# 07_LMS7002M_Power.net
KiCad netlist of a schematic drawn in Altium Designer
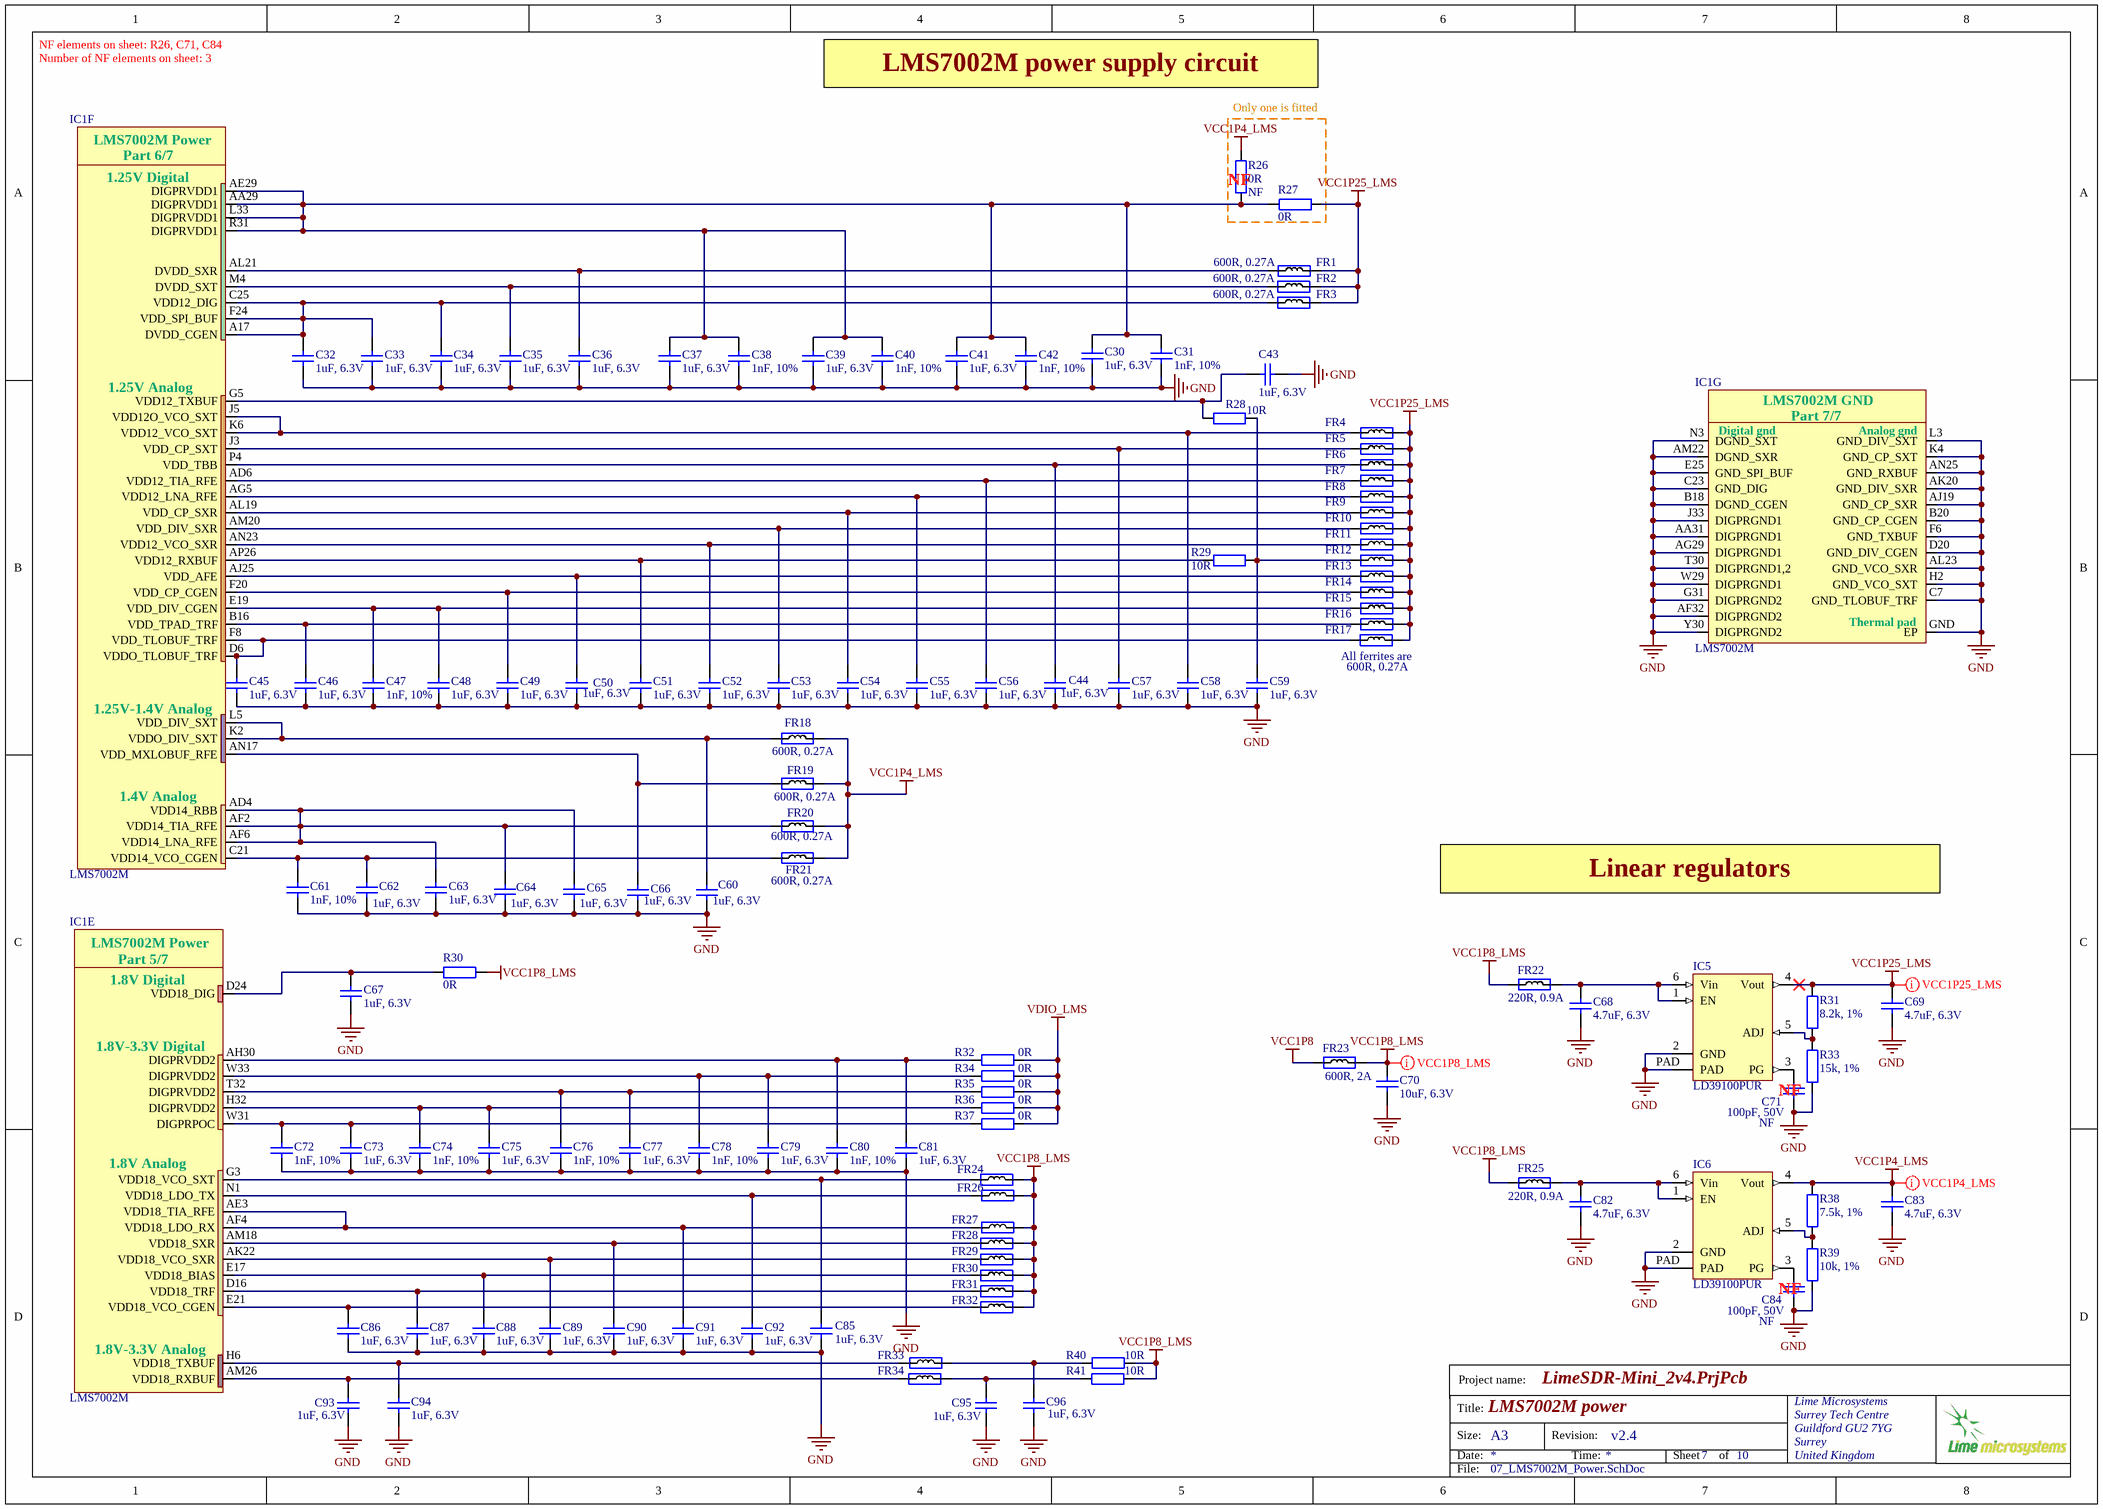
[diagram p0: 07_LMS7002M_Power.SchDoc]

(export (version "E")
  (design (tool "Eeschema 10.0.6"))
  (components
    (comp (ref "C30")
      (value "1uF, 6.3V")
      (footprint "CAP0201")
      (fields (field (name "TOLERANCE") "±20%") (field (name "MANUFACTURER") "TDK Corporation"))
      (libsource (lib "LimeMicroAltiumLib_schLib") (part "Cap_0402"))
    )
    (comp (ref "C31")
      (value "1nF, 10%")
      (footprint "CAP0201")
      (fields (field (name "TOLERANCE") "±10%") (field (name "MANUFACTURER") "TDK Corporation"))
      (libsource (lib "LimeMicroAltiumLib_schLib") (part "Cap_0402"))
    )
    (comp (ref "C32")
      (value "1uF, 6.3V")
      (footprint "CAP0201")
      (fields (field (name "TOLERANCE") "±20%") (field (name "MANUFACTURER") "TDK Corporation"))
      (libsource (lib "LimeMicroAltiumLib_schLib") (part "Cap_0402"))
    )
    (comp (ref "C33")
      (value "1uF, 6.3V")
      (footprint "CAP0201")
      (fields (field (name "TOLERANCE") "±20%") (field (name "MANUFACTURER") "TDK Corporation"))
      (libsource (lib "LimeMicroAltiumLib_schLib") (part "Cap_0402"))
    )
    (comp (ref "C34")
      (value "1uF, 6.3V")
      (footprint "CAP0201")
      (fields (field (name "TOLERANCE") "±20%") (field (name "MANUFACTURER") "TDK Corporation"))
      (libsource (lib "LimeMicroAltiumLib_schLib") (part "Cap_0402"))
    )
    (comp (ref "C35")
      (value "1uF, 6.3V")
      (footprint "CAP0201")
      (fields (field (name "TOLERANCE") "±20%") (field (name "MANUFACTURER") "TDK Corporation"))
      (libsource (lib "LimeMicroAltiumLib_schLib") (part "Cap_0402"))
    )
    (comp (ref "C36")
      (value "1uF, 6.3V")
      (footprint "CAP0201")
      (fields (field (name "TOLERANCE") "±20%") (field (name "MANUFACTURER") "TDK Corporation"))
      (libsource (lib "LimeMicroAltiumLib_schLib") (part "Cap_0402"))
    )
    (comp (ref "C37")
      (value "1uF, 6.3V")
      (footprint "CAP0201")
      (fields (field (name "TOLERANCE") "±20%") (field (name "MANUFACTURER") "TDK Corporation"))
      (libsource (lib "LimeMicroAltiumLib_schLib") (part "Cap_0402"))
    )
    (comp (ref "C38")
      (value "1nF, 10%")
      (footprint "CAP0201")
      (fields (field (name "TOLERANCE") "±10%") (field (name "MANUFACTURER") "TDK Corporation"))
      (libsource (lib "LimeMicroAltiumLib_schLib") (part "Cap_0402"))
    )
    (comp (ref "C39")
      (value "1uF, 6.3V")
      (footprint "CAP0201")
      (fields (field (name "TOLERANCE") "±20%") (field (name "MANUFACTURER") "TDK Corporation"))
      (libsource (lib "LimeMicroAltiumLib_schLib") (part "Cap_0402"))
    )
    (comp (ref "C40")
      (value "1nF, 10%")
      (footprint "CAP0201")
      (fields (field (name "TOLERANCE") "±10%") (field (name "MANUFACTURER") "TDK Corporation"))
      (libsource (lib "LimeMicroAltiumLib_schLib") (part "Cap_0402"))
    )
    (comp (ref "C41")
      (value "1uF, 6.3V")
      (footprint "CAP0201")
      (fields (field (name "TOLERANCE") "±20%") (field (name "MANUFACTURER") "TDK Corporation"))
      (libsource (lib "LimeMicroAltiumLib_schLib") (part "Cap_0402"))
    )
    (comp (ref "C42")
      (value "1nF, 10%")
      (footprint "CAP0201")
      (fields (field (name "TOLERANCE") "±10%") (field (name "MANUFACTURER") "TDK Corporation"))
      (libsource (lib "LimeMicroAltiumLib_schLib") (part "Cap_0402"))
    )
    (comp (ref "C43")
      (value "1uF, 6.3V")
      (footprint "CAP0201")
      (fields (field (name "TOLERANCE") "±20%") (field (name "MANUFACTURER") "TDK Corporation"))
      (libsource (lib "LimeMicroAltiumLib_schLib") (part "Cap_0402"))
    )
    (comp (ref "C44")
      (value "1uF, 6.3V")
      (footprint "CAP0201")
      (fields (field (name "TOLERANCE") "±20%") (field (name "MANUFACTURER") "TDK Corporation"))
      (libsource (lib "LimeMicroAltiumLib_schLib") (part "Cap_0402"))
    )
    (comp (ref "C45")
      (value "1uF, 6.3V")
      (footprint "CAP0201")
      (fields (field (name "TOLERANCE") "±20%") (field (name "MANUFACTURER") "TDK Corporation"))
      (libsource (lib "LimeMicroAltiumLib_schLib") (part "Cap_0402"))
    )
    (comp (ref "C46")
      (value "1uF, 6.3V")
      (footprint "CAP0201")
      (fields (field (name "TOLERANCE") "±20%") (field (name "MANUFACTURER") "TDK Corporation"))
      (libsource (lib "LimeMicroAltiumLib_schLib") (part "Cap_0402"))
    )
    (comp (ref "C47")
      (value "1nF, 10%")
      (footprint "CAP0201")
      (fields (field (name "TOLERANCE") "±10%") (field (name "MANUFACTURER") "TDK Corporation"))
      (libsource (lib "LimeMicroAltiumLib_schLib") (part "Cap_0402"))
    )
    (comp (ref "C48")
      (value "1uF, 6.3V")
      (footprint "CAP0201")
      (fields (field (name "TOLERANCE") "±20%") (field (name "MANUFACTURER") "TDK Corporation"))
      (libsource (lib "LimeMicroAltiumLib_schLib") (part "Cap_0402"))
    )
    (comp (ref "C49")
      (value "1uF, 6.3V")
      (footprint "CAP0201")
      (fields (field (name "TOLERANCE") "±20%") (field (name "MANUFACTURER") "TDK Corporation"))
      (libsource (lib "LimeMicroAltiumLib_schLib") (part "Cap_0402"))
    )
    (comp (ref "C50")
      (value "1uF, 6.3V")
      (footprint "CAP0201")
      (fields (field (name "TOLERANCE") "±20%") (field (name "MANUFACTURER") "TDK Corporation"))
      (libsource (lib "LimeMicroAltiumLib_schLib") (part "Cap_0402"))
    )
    (comp (ref "C51")
      (value "1uF, 6.3V")
      (footprint "CAP0201")
      (fields (field (name "TOLERANCE") "±20%") (field (name "MANUFACTURER") "TDK Corporation"))
      (libsource (lib "LimeMicroAltiumLib_schLib") (part "Cap_0402"))
    )
    (comp (ref "C52")
      (value "1uF, 6.3V")
      (footprint "CAP0201")
      (fields (field (name "TOLERANCE") "±20%") (field (name "MANUFACTURER") "TDK Corporation"))
      (libsource (lib "LimeMicroAltiumLib_schLib") (part "Cap_0402"))
    )
    (comp (ref "C53")
      (value "1uF, 6.3V")
      (footprint "CAP0201")
      (fields (field (name "TOLERANCE") "±20%") (field (name "MANUFACTURER") "TDK Corporation"))
      (libsource (lib "LimeMicroAltiumLib_schLib") (part "Cap_0402"))
    )
    (comp (ref "C54")
      (value "1uF, 6.3V")
      (footprint "CAP0201")
      (fields (field (name "TOLERANCE") "±20%") (field (name "MANUFACTURER") "TDK Corporation"))
      (libsource (lib "LimeMicroAltiumLib_schLib") (part "Cap_0402"))
    )
    (comp (ref "C55")
      (value "1uF, 6.3V")
      (footprint "CAP0201")
      (fields (field (name "TOLERANCE") "±20%") (field (name "MANUFACTURER") "TDK Corporation"))
      (libsource (lib "LimeMicroAltiumLib_schLib") (part "Cap_0402"))
    )
    (comp (ref "C56")
      (value "1uF, 6.3V")
      (footprint "CAP0201")
      (fields (field (name "TOLERANCE") "±20%") (field (name "MANUFACTURER") "TDK Corporation"))
      (libsource (lib "LimeMicroAltiumLib_schLib") (part "Cap_0402"))
    )
    (comp (ref "C57")
      (value "1uF, 6.3V")
      (footprint "CAP0201")
      (fields (field (name "TOLERANCE") "±20%") (field (name "MANUFACTURER") "TDK Corporation"))
      (libsource (lib "LimeMicroAltiumLib_schLib") (part "Cap_0402"))
    )
    (comp (ref "C58")
      (value "1uF, 6.3V")
      (footprint "CAP0201")
      (fields (field (name "TOLERANCE") "±20%") (field (name "MANUFACTURER") "TDK Corporation"))
      (libsource (lib "LimeMicroAltiumLib_schLib") (part "Cap_0402"))
    )
    (comp (ref "C59")
      (value "1uF, 6.3V")
      (footprint "CAP0201")
      (fields (field (name "TOLERANCE") "±20%") (field (name "MANUFACTURER") "TDK Corporation"))
      (libsource (lib "LimeMicroAltiumLib_schLib") (part "Cap_0402"))
    )
    (comp (ref "C60")
      (value "1uF, 6.3V")
      (footprint "CAP0201")
      (fields (field (name "TOLERANCE") "±20%") (field (name "MANUFACTURER") "TDK Corporation"))
      (libsource (lib "LimeMicroAltiumLib_schLib") (part "Cap_0402"))
    )
    (comp (ref "C61")
      (value "1nF, 10%")
      (footprint "CAP0201")
      (fields (field (name "TOLERANCE") "±10%") (field (name "MANUFACTURER") "TDK Corporation"))
      (libsource (lib "LimeMicroAltiumLib_schLib") (part "Cap_0402"))
    )
    (comp (ref "C62")
      (value "1uF, 6.3V")
      (footprint "CAP0201")
      (fields (field (name "TOLERANCE") "±20%") (field (name "MANUFACTURER") "TDK Corporation"))
      (libsource (lib "LimeMicroAltiumLib_schLib") (part "Cap_0402"))
    )
    (comp (ref "C63")
      (value "1uF, 6.3V")
      (footprint "CAP0201")
      (fields (field (name "TOLERANCE") "±20%") (field (name "MANUFACTURER") "TDK Corporation"))
      (libsource (lib "LimeMicroAltiumLib_schLib") (part "Cap_0402"))
    )
    (comp (ref "C64")
      (value "1uF, 6.3V")
      (footprint "CAP0201")
      (fields (field (name "TOLERANCE") "±20%") (field (name "MANUFACTURER") "TDK Corporation"))
      (libsource (lib "LimeMicroAltiumLib_schLib") (part "Cap_0402"))
    )
    (comp (ref "C65")
      (value "1uF, 6.3V")
      (footprint "CAP0201")
      (fields (field (name "TOLERANCE") "±20%") (field (name "MANUFACTURER") "TDK Corporation"))
      (libsource (lib "LimeMicroAltiumLib_schLib") (part "Cap_0402"))
    )
    (comp (ref "C66")
      (value "1uF, 6.3V")
      (footprint "CAP0201")
      (fields (field (name "TOLERANCE") "±20%") (field (name "MANUFACTURER") "TDK Corporation"))
      (libsource (lib "LimeMicroAltiumLib_schLib") (part "Cap_0402"))
    )
    (comp (ref "C67")
      (value "1uF, 6.3V")
      (footprint "CAP0201")
      (fields (field (name "TOLERANCE") "±20%") (field (name "MANUFACTURER") "TDK Corporation"))
      (libsource (lib "LimeMicroAltiumLib_schLib") (part "Cap_0402"))
    )
    (comp (ref "C68")
      (value "4.7uF, 6.3V")
      (footprint "CAP0402")
      (fields
        (field (name "MANUFACTURER") "Murata Electronics North America")
        (field (name "TOLERANCE") "±20%")
      )
      (libsource (lib "LimeMicroAltiumLib_schLib") (part "Cap_0402"))
    )
    (comp (ref "C69")
      (value "4.7uF, 6.3V")
      (footprint "CAP0402")
      (fields
        (field (name "MANUFACTURER") "Murata Electronics North America")
        (field (name "TOLERANCE") "±20%")
      )
      (libsource (lib "LimeMicroAltiumLib_schLib") (part "Cap_0402"))
    )
    (comp (ref "C70")
      (value "10uF, 6.3V")
      (footprint "CAP0603")
      (fields (field (name "TOLERANCE") "±20%") (field (name "MANUFACTURER") "Yageo"))
      (libsource (lib "LimeFPGAboard_schLib") (part "Cap_0603"))
    )
    (comp (ref "C71")
      (value "100pF, 50V")
      (footprint "CAP0402")
      (fields
        (field (name "ASSEMBLY INFO") "NF")
        (field (name "MANUFACTURER") "Yageo")
        (field (name "TOLERANCE") "±5%")
      )
      (libsource (lib "LimeMicroAltiumLib_schLib") (part "Cap_0402"))
    )
    (comp (ref "C72")
      (value "1nF, 10%")
      (footprint "CAP0201")
      (fields (field (name "TOLERANCE") "±10%") (field (name "MANUFACTURER") "TDK Corporation"))
      (libsource (lib "LimeMicroAltiumLib_schLib") (part "Cap_0402"))
    )
    (comp (ref "C73")
      (value "1uF, 6.3V")
      (footprint "CAP0201")
      (fields (field (name "TOLERANCE") "±20%") (field (name "MANUFACTURER") "TDK Corporation"))
      (libsource (lib "LimeMicroAltiumLib_schLib") (part "Cap_0402"))
    )
    (comp (ref "C74")
      (value "1nF, 10%")
      (footprint "CAP0201")
      (fields (field (name "TOLERANCE") "±10%") (field (name "MANUFACTURER") "TDK Corporation"))
      (libsource (lib "LimeMicroAltiumLib_schLib") (part "Cap_0402"))
    )
    (comp (ref "C75")
      (value "1uF, 6.3V")
      (footprint "CAP0201")
      (fields (field (name "TOLERANCE") "±20%") (field (name "MANUFACTURER") "TDK Corporation"))
      (libsource (lib "LimeMicroAltiumLib_schLib") (part "Cap_0402"))
    )
    (comp (ref "C76")
      (value "1nF, 10%")
      (footprint "CAP0201")
      (fields (field (name "TOLERANCE") "±10%") (field (name "MANUFACTURER") "TDK Corporation"))
      (libsource (lib "LimeMicroAltiumLib_schLib") (part "Cap_0402"))
    )
    (comp (ref "C77")
      (value "1uF, 6.3V")
      (footprint "CAP0201")
      (fields (field (name "TOLERANCE") "±20%") (field (name "MANUFACTURER") "TDK Corporation"))
      (libsource (lib "LimeMicroAltiumLib_schLib") (part "Cap_0402"))
    )
    (comp (ref "C78")
      (value "1nF, 10%")
      (footprint "CAP0201")
      (fields (field (name "TOLERANCE") "±10%") (field (name "MANUFACTURER") "TDK Corporation"))
      (libsource (lib "LimeMicroAltiumLib_schLib") (part "Cap_0402"))
    )
    (comp (ref "C79")
      (value "1uF, 6.3V")
      (footprint "CAP0201")
      (fields (field (name "TOLERANCE") "±20%") (field (name "MANUFACTURER") "TDK Corporation"))
      (libsource (lib "LimeMicroAltiumLib_schLib") (part "Cap_0402"))
    )
    (comp (ref "C80")
      (value "1nF, 10%")
      (footprint "CAP0201")
      (fields (field (name "TOLERANCE") "±10%") (field (name "MANUFACTURER") "TDK Corporation"))
      (libsource (lib "LimeMicroAltiumLib_schLib") (part "Cap_0402"))
    )
    (comp (ref "C81")
      (value "1uF, 6.3V")
      (footprint "CAP0201")
      (fields (field (name "TOLERANCE") "±20%") (field (name "MANUFACTURER") "TDK Corporation"))
      (libsource (lib "LimeMicroAltiumLib_schLib") (part "Cap_0402"))
    )
    (comp (ref "C82")
      (value "4.7uF, 6.3V")
      (footprint "CAP0402")
      (fields
        (field (name "MANUFACTURER") "Murata Electronics North America")
        (field (name "TOLERANCE") "±20%")
      )
      (libsource (lib "LimeMicroAltiumLib_schLib") (part "Cap_0402"))
    )
    (comp (ref "C83")
      (value "4.7uF, 6.3V")
      (footprint "CAP0402")
      (fields
        (field (name "MANUFACTURER") "Murata Electronics North America")
        (field (name "TOLERANCE") "±20%")
      )
      (libsource (lib "LimeMicroAltiumLib_schLib") (part "Cap_0402"))
    )
    (comp (ref "C84")
      (value "100pF, 50V")
      (footprint "CAP0402")
      (fields
        (field (name "ASSEMBLY INFO") "NF")
        (field (name "MANUFACTURER") "Yageo")
        (field (name "TOLERANCE") "±5%")
      )
      (libsource (lib "LimeMicroAltiumLib_schLib") (part "Cap_0402"))
    )
    (comp (ref "C85")
      (value "1uF, 6.3V")
      (footprint "CAP0201")
      (fields (field (name "TOLERANCE") "±20%") (field (name "MANUFACTURER") "TDK Corporation"))
      (libsource (lib "LimeMicroAltiumLib_schLib") (part "Cap_0402"))
    )
    (comp (ref "C86")
      (value "1uF, 6.3V")
      (footprint "CAP0201")
      (fields (field (name "TOLERANCE") "±20%") (field (name "MANUFACTURER") "TDK Corporation"))
      (libsource (lib "LimeMicroAltiumLib_schLib") (part "Cap_0402"))
    )
    (comp (ref "C87")
      (value "1uF, 6.3V")
      (footprint "CAP0201")
      (fields (field (name "TOLERANCE") "±20%") (field (name "MANUFACTURER") "TDK Corporation"))
      (libsource (lib "LimeMicroAltiumLib_schLib") (part "Cap_0402"))
    )
    (comp (ref "C88")
      (value "1uF, 6.3V")
      (footprint "CAP0201")
      (fields (field (name "TOLERANCE") "±20%") (field (name "MANUFACTURER") "TDK Corporation"))
      (libsource (lib "LimeMicroAltiumLib_schLib") (part "Cap_0402"))
    )
    (comp (ref "C89")
      (value "1uF, 6.3V")
      (footprint "CAP0201")
      (fields (field (name "TOLERANCE") "±20%") (field (name "MANUFACTURER") "TDK Corporation"))
      (libsource (lib "LimeMicroAltiumLib_schLib") (part "Cap_0402"))
    )
    (comp (ref "C90")
      (value "1uF, 6.3V")
      (footprint "CAP0201")
      (fields (field (name "TOLERANCE") "±20%") (field (name "MANUFACTURER") "TDK Corporation"))
      (libsource (lib "LimeMicroAltiumLib_schLib") (part "Cap_0402"))
    )
    (comp (ref "C91")
      (value "1uF, 6.3V")
      (footprint "CAP0201")
      (fields (field (name "TOLERANCE") "±20%") (field (name "MANUFACTURER") "TDK Corporation"))
      (libsource (lib "LimeMicroAltiumLib_schLib") (part "Cap_0402"))
    )
    (comp (ref "C92")
      (value "1uF, 6.3V")
      (footprint "CAP0201")
      (fields (field (name "TOLERANCE") "±20%") (field (name "MANUFACTURER") "TDK Corporation"))
      (libsource (lib "LimeMicroAltiumLib_schLib") (part "Cap_0402"))
    )
    (comp (ref "C93")
      (value "1uF, 6.3V")
      (footprint "CAP0201")
      (fields (field (name "TOLERANCE") "±20%") (field (name "MANUFACTURER") "TDK Corporation"))
      (libsource (lib "LimeMicroAltiumLib_schLib") (part "Cap_0402"))
    )
    (comp (ref "C94")
      (value "1uF, 6.3V")
      (footprint "CAP0201")
      (fields (field (name "TOLERANCE") "±20%") (field (name "MANUFACTURER") "TDK Corporation"))
      (libsource (lib "LimeMicroAltiumLib_schLib") (part "Cap_0402"))
    )
    (comp (ref "C95")
      (value "1uF, 6.3V")
      (footprint "CAP0201")
      (fields (field (name "TOLERANCE") "±20%") (field (name "MANUFACTURER") "TDK Corporation"))
      (libsource (lib "LimeMicroAltiumLib_schLib") (part "Cap_0402"))
    )
    (comp (ref "C96")
      (value "1uF, 6.3V")
      (footprint "CAP0201")
      (fields (field (name "TOLERANCE") "±20%") (field (name "MANUFACTURER") "TDK Corporation"))
      (libsource (lib "LimeMicroAltiumLib_schLib") (part "Cap_0402"))
    )
    (comp (ref "FR1")
      (value "600R, 0.27A")
      (footprint "RES0201")
      (fields (field (name "MANUFACTURER") "Taiyo Yuden"))
      (libsource (lib "LimeMicroAltiumLib_schLib") (part "Ferrite"))
    )
    (comp (ref "FR2")
      (value "600R, 0.27A")
      (footprint "RES0201")
      (fields (field (name "MANUFACTURER") "Taiyo Yuden"))
      (libsource (lib "LimeMicroAltiumLib_schLib") (part "Ferrite"))
    )
    (comp (ref "FR3")
      (value "600R, 0.27A")
      (footprint "RES0201")
      (fields (field (name "MANUFACTURER") "Taiyo Yuden"))
      (libsource (lib "LimeMicroAltiumLib_schLib") (part "Ferrite"))
    )
    (comp (ref "FR4")
      (value "600R, 0.27A")
      (footprint "RES0201")
      (fields (field (name "MANUFACTURER") "Taiyo Yuden"))
      (libsource (lib "LimeMicroAltiumLib_schLib") (part "Ferrite"))
    )
    (comp (ref "FR5")
      (value "600R, 0.27A")
      (footprint "RES0201")
      (fields (field (name "MANUFACTURER") "Taiyo Yuden"))
      (libsource (lib "LimeMicroAltiumLib_schLib") (part "Ferrite"))
    )
    (comp (ref "FR6")
      (value "600R, 0.27A")
      (footprint "RES0201")
      (fields (field (name "MANUFACTURER") "Taiyo Yuden"))
      (libsource (lib "LimeMicroAltiumLib_schLib") (part "Ferrite"))
    )
    (comp (ref "FR7")
      (value "600R, 0.27A")
      (footprint "RES0201")
      (fields (field (name "MANUFACTURER") "Taiyo Yuden"))
      (libsource (lib "LimeMicroAltiumLib_schLib") (part "Ferrite"))
    )
    (comp (ref "FR8")
      (value "600R, 0.27A")
      (footprint "RES0201")
      (fields (field (name "MANUFACTURER") "Taiyo Yuden"))
      (libsource (lib "LimeMicroAltiumLib_schLib") (part "Ferrite"))
    )
    (comp (ref "FR9")
      (value "600R, 0.27A")
      (footprint "RES0201")
      (fields (field (name "MANUFACTURER") "Taiyo Yuden"))
      (libsource (lib "LimeMicroAltiumLib_schLib") (part "Ferrite"))
    )
    (comp (ref "FR10")
      (value "600R, 0.27A")
      (footprint "RES0201")
      (fields (field (name "MANUFACTURER") "Taiyo Yuden"))
      (libsource (lib "LimeMicroAltiumLib_schLib") (part "Ferrite"))
    )
    (comp (ref "FR11")
      (value "600R, 0.27A")
      (footprint "RES0201")
      (fields (field (name "MANUFACTURER") "Taiyo Yuden"))
      (libsource (lib "LimeMicroAltiumLib_schLib") (part "Ferrite"))
    )
    (comp (ref "FR12")
      (value "600R, 0.27A")
      (footprint "RES0201")
      (fields (field (name "MANUFACTURER") "Taiyo Yuden"))
      (libsource (lib "LimeMicroAltiumLib_schLib") (part "Ferrite"))
    )
    (comp (ref "FR13")
      (value "600R, 0.27A")
      (footprint "RES0201")
      (fields (field (name "MANUFACTURER") "Taiyo Yuden"))
      (libsource (lib "LimeMicroAltiumLib_schLib") (part "Ferrite"))
    )
    (comp (ref "FR14")
      (value "600R, 0.27A")
      (footprint "RES0201")
      (fields (field (name "MANUFACTURER") "Taiyo Yuden"))
      (libsource (lib "LimeMicroAltiumLib_schLib") (part "Ferrite"))
    )
    (comp (ref "FR15")
      (value "600R, 0.27A")
      (footprint "RES0201")
      (fields (field (name "MANUFACTURER") "Taiyo Yuden"))
      (libsource (lib "LimeMicroAltiumLib_schLib") (part "Ferrite"))
    )
    (comp (ref "FR16")
      (value "600R, 0.27A")
      (footprint "RES0201")
      (fields (field (name "MANUFACTURER") "Taiyo Yuden"))
      (libsource (lib "LimeMicroAltiumLib_schLib") (part "Ferrite"))
    )
    (comp (ref "FR17")
      (value "600R, 0.27A")
      (footprint "RES0201")
      (fields (field (name "MANUFACTURER") "Taiyo Yuden"))
      (libsource (lib "LimeMicroAltiumLib_schLib") (part "Ferrite"))
    )
    (comp (ref "FR18")
      (value "600R, 0.27A")
      (footprint "RES0201")
      (fields (field (name "MANUFACTURER") "Taiyo Yuden"))
      (libsource (lib "LimeMicroAltiumLib_schLib") (part "Ferrite"))
    )
    (comp (ref "FR19")
      (value "600R, 0.27A")
      (footprint "RES0201")
      (fields (field (name "MANUFACTURER") "Taiyo Yuden"))
      (libsource (lib "LimeMicroAltiumLib_schLib") (part "Ferrite"))
    )
    (comp (ref "FR20")
      (value "600R, 0.27A")
      (footprint "RES0201")
      (fields (field (name "MANUFACTURER") "Taiyo Yuden"))
      (libsource (lib "LimeMicroAltiumLib_schLib") (part "Ferrite"))
    )
    (comp (ref "FR21")
      (value "600R, 0.27A")
      (footprint "RES0201")
      (fields (field (name "MANUFACTURER") "Taiyo Yuden"))
      (libsource (lib "LimeMicroAltiumLib_schLib") (part "Ferrite"))
    )
    (comp (ref "FR22")
      (value "220R, 0.9A")
      (footprint "RES0402")
      (fields (field (name "MANUFACTURER") "TDK Corporation"))
      (libsource (lib "LimeFPGAboard_schLib") (part "Ferrite"))
    )
    (comp (ref "FR23")
      (value "600R, 2A")
      (footprint "RES0805")
      (fields (field (name "MANUFACTURER") "TDK Corporation"))
      (libsource (lib "LimeMicroAltiumLib_schLib") (part "Ferrite"))
    )
    (comp (ref "FR24")
      (value "600R, 0.27A")
      (footprint "RES0201")
      (fields (field (name "MANUFACTURER") "Taiyo Yuden"))
      (libsource (lib "LimeMicroAltiumLib_schLib") (part "Ferrite"))
    )
    (comp (ref "FR25")
      (value "220R, 0.9A")
      (footprint "RES0402")
      (fields (field (name "MANUFACTURER") "TDK Corporation"))
      (libsource (lib "LimeFPGAboard_schLib") (part "Ferrite"))
    )
    (comp (ref "FR26")
      (value "600R, 0.27A")
      (footprint "RES0201")
      (fields (field (name "MANUFACTURER") "Taiyo Yuden"))
      (libsource (lib "") (part "Ferrite_1"))
    )
    (comp (ref "FR27")
      (value "600R, 0.27A")
      (footprint "RES0201")
      (fields (field (name "MANUFACTURER") "Taiyo Yuden"))
      (libsource (lib "") (part "Ferrite_1"))
    )
    (comp (ref "FR28")
      (value "600R, 0.27A")
      (footprint "RES0201")
      (fields (field (name "MANUFACTURER") "Taiyo Yuden"))
      (libsource (lib "LimeMicroAltiumLib_schLib") (part "Ferrite"))
    )
    (comp (ref "FR29")
      (value "600R, 0.27A")
      (footprint "RES0201")
      (fields (field (name "MANUFACTURER") "Taiyo Yuden"))
      (libsource (lib "LimeMicroAltiumLib_schLib") (part "Ferrite"))
    )
    (comp (ref "FR30")
      (value "600R, 0.27A")
      (footprint "RES0201")
      (fields (field (name "MANUFACTURER") "Taiyo Yuden"))
      (libsource (lib "LimeMicroAltiumLib_schLib") (part "Ferrite"))
    )
    (comp (ref "FR31")
      (value "600R, 0.27A")
      (footprint "RES0201")
      (fields (field (name "MANUFACTURER") "Taiyo Yuden"))
      (libsource (lib "LimeMicroAltiumLib_schLib") (part "Ferrite"))
    )
    (comp (ref "FR32")
      (value "600R, 0.27A")
      (footprint "RES0201")
      (fields (field (name "MANUFACTURER") "Taiyo Yuden"))
      (libsource (lib "LimeMicroAltiumLib_schLib") (part "Ferrite"))
    )
    (comp (ref "FR33")
      (value "600R, 0.27A")
      (footprint "RES0201")
      (fields (field (name "MANUFACTURER") "Taiyo Yuden"))
      (libsource (lib "") (part "Ferrite_1"))
    )
    (comp (ref "FR34")
      (value "600R, 0.27A")
      (footprint "RES0201")
      (fields (field (name "MANUFACTURER") "Taiyo Yuden"))
      (libsource (lib "LimeMicroAltiumLib_schLib") (part "Ferrite"))
    )
    (comp (ref "IC1")
      (value "LMS7002M")
      (footprint "LMS7002M_v5")
      (description "Schematic symbol revision 4. Default footprint - 0.31mm pad")
      (fields (field (name "MANUFACTURER") "Lime Microsystems"))
      (libsource (lib "LimeMicroAltiumLib_schLib_r04") (part "LMS7002Mr4"))
    )
    (comp (ref "IC5")
      (value "LD39100PUR")
      (footprint "LD39100PUR")
      (fields (field (name "MANUFACTURER") "STMicroelectronics"))
      (libsource (lib "LimeMicroAltiumLib_schLib") (part "LD39100PUR"))
    )
    (comp (ref "IC6")
      (value "LD39100PUR")
      (footprint "LD39100PUR")
      (fields (field (name "MANUFACTURER") "STMicroelectronics"))
      (libsource (lib "LimeMicroAltiumLib_schLib") (part "LD39100PUR"))
    )
    (comp (ref "R26")
      (value "0R")
      (footprint "RES0402")
      (fields
        (field (name "ASSEMBLY INFO") "NF")
        (field (name "MANUFACTURER") "Yageo")
        (field (name "TOLERANCE") "Jumper")
      )
      (libsource (lib "LimeMicroAltiumLib_schLib") (part "Res_0402"))
    )
    (comp (ref "R27")
      (value "0R")
      (footprint "RES0402")
      (fields (field (name "MANUFACTURER") "Yageo") (field (name "TOLERANCE") "Jumper"))
      (libsource (lib "LimeMicroAltiumLib_schLib") (part "Res_0402"))
    )
    (comp (ref "R28")
      (value "10R")
      (footprint "RES0201")
      (fields
        (field (name "MANUFACTURER") "Panasonic Electronic Components")
        (field (name "TOLERANCE") "±1%")
      )
      (libsource (lib "LimeMicroAltiumLib_schLib") (part "Res_0402"))
    )
    (comp (ref "R29")
      (value "10R")
      (footprint "RES0201")
      (fields
        (field (name "MANUFACTURER") "Panasonic Electronic Components")
        (field (name "TOLERANCE") "±1%")
      )
      (libsource (lib "LimeMicroAltiumLib_schLib") (part "Res_0402"))
    )
    (comp (ref "R30")
      (value "0R")
      (footprint "RES0201")
      (fields (field (name "MANUFACTURER") "Rohm Semiconductor") (field (name "TOLERANCE") "Jumper"))
      (libsource (lib "LimeMicroAltiumLib_schLib") (part "Res_0402"))
    )
    (comp (ref "R31")
      (value "8.2k, 1%")
      (footprint "RES0402")
      (fields (field (name "MANUFACTURER") "Yageo") (field (name "TOLERANCE") "±1%"))
      (libsource (lib "LimeMicroAltiumLib_schLib") (part "Res_0402"))
    )
    (comp (ref "R32")
      (value "0R")
      (footprint "RES0402")
      (fields (field (name "MANUFACTURER") "Yageo") (field (name "TOLERANCE") "Jumper"))
      (libsource (lib "LimeMicroAltiumLib_schLib") (part "Res_0402"))
    )
    (comp (ref "R33")
      (value "15k, 1%")
      (footprint "RES0402")
      (fields (field (name "TOLERANCE") "±1%") (field (name "MANUFACTURER") "Yageo"))
      (libsource (lib "LimeMicroAltiumLib_schLib") (part "Res_0402"))
    )
    (comp (ref "R34")
      (value "0R")
      (footprint "RES0402")
      (fields (field (name "MANUFACTURER") "Yageo") (field (name "TOLERANCE") "Jumper"))
      (libsource (lib "LimeMicroAltiumLib_schLib") (part "Res_0402"))
    )
    (comp (ref "R35")
      (value "0R")
      (footprint "RES0402")
      (fields (field (name "MANUFACTURER") "Yageo") (field (name "TOLERANCE") "Jumper"))
      (libsource (lib "LimeMicroAltiumLib_schLib") (part "Res_0402"))
    )
    (comp (ref "R36")
      (value "0R")
      (footprint "RES0402")
      (fields (field (name "MANUFACTURER") "Yageo") (field (name "TOLERANCE") "Jumper"))
      (libsource (lib "LimeMicroAltiumLib_schLib") (part "Res_0402"))
    )
    (comp (ref "R37")
      (value "0R")
      (footprint "RES0402")
      (fields (field (name "MANUFACTURER") "Yageo") (field (name "TOLERANCE") "Jumper"))
      (libsource (lib "LimeMicroAltiumLib_schLib") (part "Res_0402"))
    )
    (comp (ref "R38")
      (value "7.5k, 1%")
      (footprint "RES0402")
      (fields (field (name "MANUFACTURER") "Yageo") (field (name "TOLERANCE") "±1%"))
      (libsource (lib "LimeMicroAltiumLib_schLib") (part "Res_0402"))
    )
    (comp (ref "R39")
      (value "10k, 1%")
      (footprint "RES0402")
      (fields (field (name "MANUFACTURER") "Yageo") (field (name "TOLERANCE") "±1%"))
      (libsource (lib "LimeMicroAltiumLib_schLib") (part "Res_0402"))
    )
    (comp (ref "R40")
      (value "10R")
      (footprint "RES0201")
      (fields
        (field (name "MANUFACTURER") "Panasonic Electronic Components")
        (field (name "TOLERANCE") "±1%")
      )
      (libsource (lib "LimeMicroAltiumLib_schLib") (part "Res_0402"))
    )
    (comp (ref "R41")
      (value "10R")
      (footprint "RES0201")
      (fields
        (field (name "MANUFACTURER") "Panasonic Electronic Components")
        (field (name "TOLERANCE") "±1%")
      )
      (libsource (lib "LimeMicroAltiumLib_schLib") (part "Res_0402"))
    )
  )
  (nets
    (net (code "1") (name "GND") (class "Default")
      (node (ref "C30") (pin "2") (pinfunction "2_2") (pintype "passive"))
      (node (ref "C31") (pin "2") (pinfunction "2_2") (pintype "passive"))
      (node (ref "C32") (pin "2") (pinfunction "2_2") (pintype "passive"))
      (node (ref "C33") (pin "2") (pinfunction "2_2") (pintype "passive"))
      (node (ref "C34") (pin "2") (pinfunction "2_2") (pintype "passive"))
      (node (ref "C35") (pin "1") (pinfunction "1_1") (pintype "passive"))
      (node (ref "C36") (pin "2") (pinfunction "2_2") (pintype "passive"))
      (node (ref "C37") (pin "2") (pinfunction "2_2") (pintype "passive"))
      (node (ref "C38") (pin "2") (pinfunction "2_2") (pintype "passive"))
      (node (ref "C39") (pin "2") (pinfunction "2_2") (pintype "passive"))
      (node (ref "C40") (pin "2") (pinfunction "2_2") (pintype "passive"))
      (node (ref "C41") (pin "2") (pinfunction "2_2") (pintype "passive"))
      (node (ref "C42") (pin "2") (pinfunction "2_2") (pintype "passive"))
      (node (ref "C43") (pin "2") (pinfunction "2_2") (pintype "passive"))
      (node (ref "C44") (pin "2") (pinfunction "2_2") (pintype "passive"))
      (node (ref "C45") (pin "2") (pinfunction "2_2") (pintype "passive"))
      (node (ref "C46") (pin "2") (pinfunction "2_2") (pintype "passive"))
      (node (ref "C47") (pin "2") (pinfunction "2_2") (pintype "passive"))
      (node (ref "C48") (pin "2") (pinfunction "2_2") (pintype "passive"))
      (node (ref "C49") (pin "1") (pinfunction "1_1") (pintype "passive"))
      (node (ref "C50") (pin "2") (pinfunction "2_2") (pintype "passive"))
      (node (ref "C51") (pin "2") (pinfunction "2_2") (pintype "passive"))
      (node (ref "C52") (pin "2") (pinfunction "2_2") (pintype "passive"))
      (node (ref "C53") (pin "2") (pinfunction "2_2") (pintype "passive"))
      (node (ref "C54") (pin "2") (pinfunction "2_2") (pintype "passive"))
      (node (ref "C55") (pin "2") (pinfunction "2_2") (pintype "passive"))
      (node (ref "C56") (pin "1") (pinfunction "1_1") (pintype "passive"))
      (node (ref "C57") (pin "2") (pinfunction "2_2") (pintype "passive"))
      (node (ref "C58") (pin "1") (pinfunction "1_1") (pintype "passive"))
      (node (ref "C59") (pin "1") (pinfunction "1_1") (pintype "passive"))
      (node (ref "C60") (pin "2") (pinfunction "2_2") (pintype "passive"))
      (node (ref "C61") (pin "2") (pinfunction "2_2") (pintype "passive"))
      (node (ref "C62") (pin "2") (pinfunction "2_2") (pintype "passive"))
      (node (ref "C63") (pin "2") (pinfunction "2_2") (pintype "passive"))
      (node (ref "C64") (pin "2") (pinfunction "2_2") (pintype "passive"))
      (node (ref "C65") (pin "2") (pinfunction "2_2") (pintype "passive"))
      (node (ref "C66") (pin "2") (pinfunction "2_2") (pintype "passive"))
      (node (ref "C67") (pin "2") (pinfunction "2_2") (pintype "passive"))
      (node (ref "C68") (pin "1") (pinfunction "1_1") (pintype "passive"))
      (node (ref "C69") (pin "1") (pinfunction "1_1") (pintype "passive"))
      (node (ref "C70") (pin "1") (pinfunction "1_1") (pintype "passive"))
      (node (ref "C71") (pin "1") (pinfunction "1_1") (pintype "passive"))
      (node (ref "C72") (pin "2") (pinfunction "2_2") (pintype "passive"))
      (node (ref "C73") (pin "2") (pinfunction "2_2") (pintype "passive"))
      (node (ref "C74") (pin "2") (pinfunction "2_2") (pintype "passive"))
      (node (ref "C75") (pin "2") (pinfunction "2_2") (pintype "passive"))
      (node (ref "C76") (pin "2") (pinfunction "2_2") (pintype "passive"))
      (node (ref "C77") (pin "2") (pinfunction "2_2") (pintype "passive"))
      (node (ref "C78") (pin "2") (pinfunction "2_2") (pintype "passive"))
      (node (ref "C79") (pin "2") (pinfunction "2_2") (pintype "passive"))
      (node (ref "C80") (pin "2") (pinfunction "2_2") (pintype "passive"))
      (node (ref "C81") (pin "2") (pinfunction "2_2") (pintype "passive"))
      (node (ref "C82") (pin "1") (pinfunction "1_1") (pintype "passive"))
      (node (ref "C83") (pin "1") (pinfunction "1_1") (pintype "passive"))
      (node (ref "C84") (pin "1") (pinfunction "1_1") (pintype "passive"))
      (node (ref "C85") (pin "2") (pinfunction "2_2") (pintype "passive"))
      (node (ref "C86") (pin "2") (pinfunction "2_2") (pintype "passive"))
      (node (ref "C87") (pin "2") (pinfunction "2_2") (pintype "passive"))
      (node (ref "C88") (pin "2") (pinfunction "2_2") (pintype "passive"))
      (node (ref "C89") (pin "2") (pinfunction "2_2") (pintype "passive"))
      (node (ref "C90") (pin "2") (pinfunction "2_2") (pintype "passive"))
      (node (ref "C91") (pin "2") (pinfunction "2_2") (pintype "passive"))
      (node (ref "C92") (pin "2") (pinfunction "2_2") (pintype "passive"))
      (node (ref "C93") (pin "2") (pinfunction "2_2") (pintype "passive"))
      (node (ref "C94") (pin "2") (pinfunction "2_2") (pintype "passive"))
      (node (ref "C95") (pin "2") (pinfunction "2_2") (pintype "passive"))
      (node (ref "C96") (pin "2") (pinfunction "2_2") (pintype "passive"))
      (node (ref "IC1") (pin "AA31") (pinfunction "DIGPRGND1_AA31") (pintype "passive"))
      (node (ref "IC1") (pin "AF32") (pinfunction "DIGPRGND2_AF32") (pintype "passive"))
      (node (ref "IC1") (pin "AG29") (pinfunction "DIGPRGND1_AG29") (pintype "passive"))
      (node (ref "IC1") (pin "AJ19") (pinfunction "GND_CP_SXR_AJ19") (pintype "passive"))
      (node (ref "IC1") (pin "AK20") (pinfunction "GND_DIV_SXR_AK20") (pintype "passive"))
      (node (ref "IC1") (pin "AL23") (pinfunction "GND_VCO_SXR_AL23") (pintype "passive"))
      (node (ref "IC1") (pin "AM22") (pinfunction "DGND_SXR_AM22") (pintype "passive"))
      (node (ref "IC1") (pin "AN25") (pinfunction "GND_RXBUF_AN25") (pintype "passive"))
      (node (ref "IC1") (pin "B18") (pinfunction "DGND_CGEN_B18") (pintype "passive"))
      (node (ref "IC1") (pin "B20") (pinfunction "GND_CP_CGEN_B20") (pintype "passive"))
      (node (ref "IC1") (pin "C23") (pinfunction "GND_DIG_C23") (pintype "passive"))
      (node (ref "IC1") (pin "C7") (pinfunction "GND_TLOBUF_TRF_C7") (pintype "passive"))
      (node (ref "IC1") (pin "D20") (pinfunction "GND_DIV_CGEN_D20") (pintype "passive"))
      (node (ref "IC1") (pin "E25") (pinfunction "GND_SPI_BUF_E25") (pintype "passive"))
      (node (ref "IC1") (pin "F6") (pinfunction "GND_TXBUF_F6") (pintype "passive"))
      (node (ref "IC1") (pin "G31") (pinfunction "DIGPRGND2_G31") (pintype "passive"))
      (node (ref "IC1") (pin "GND") (pinfunction "EP_GND") (pintype "passive"))
      (node (ref "IC1") (pin "H2") (pinfunction "GND_VCO_SXT_H2") (pintype "passive"))
      (node (ref "IC1") (pin "J33") (pinfunction "DIGPRGND1_J33") (pintype "passive"))
      (node (ref "IC1") (pin "K4") (pinfunction "GND_CP_SXT_K4") (pintype "passive"))
      (node (ref "IC1") (pin "L3") (pinfunction "GND_DIV_SXT_L3") (pintype "passive"))
      (node (ref "IC1") (pin "N3") (pinfunction "DGND_SXT_N3") (pintype "passive"))
      (node (ref "IC1") (pin "T30") (pinfunction "DIGPRGND1,2_T30") (pintype "passive"))
      (node (ref "IC1") (pin "W29") (pinfunction "DIGPRGND1_W29") (pintype "passive"))
      (node (ref "IC1") (pin "Y30") (pinfunction "DIGPRGND2_Y30") (pintype "passive"))
      (node (ref "IC5") (pin "2") (pinfunction "GND_2") (pintype "passive"))
      (node (ref "IC5") (pin "PAD") (pinfunction "PAD_PAD") (pintype "passive"))
      (node (ref "IC6") (pin "2") (pinfunction "GND_2") (pintype "passive"))
      (node (ref "IC6") (pin "PAD") (pinfunction "PAD_PAD") (pintype "passive"))
      (node (ref "R33") (pin "1") (pinfunction "1_1") (pintype "passive"))
      (node (ref "R39") (pin "1") (pinfunction "1_1") (pintype "passive"))
    )
    (net (code "2") (name "Net-(C30-Pad1)") (class "Default")
      (node (ref "C30") (pin "1") (pinfunction "1_1") (pintype "passive"))
      (node (ref "C31") (pin "1") (pinfunction "1_1") (pintype "passive"))
      (node (ref "C37") (pin "1") (pinfunction "1_1") (pintype "passive"))
      (node (ref "C38") (pin "1") (pinfunction "1_1") (pintype "passive"))
      (node (ref "C39") (pin "1") (pinfunction "1_1") (pintype "passive"))
      (node (ref "C40") (pin "1") (pinfunction "1_1") (pintype "passive"))
      (node (ref "C41") (pin "1") (pinfunction "1_1") (pintype "passive"))
      (node (ref "C42") (pin "1") (pinfunction "1_1") (pintype "passive"))
      (node (ref "IC1") (pin "AA29") (pinfunction "DIGPRVDD1_AA29") (pintype "power_in"))
      (node (ref "IC1") (pin "AE29") (pinfunction "DIGPRVDD1_AE29") (pintype "power_in"))
      (node (ref "IC1") (pin "L33") (pinfunction "DIGPRVDD1_L33") (pintype "power_in"))
      (node (ref "IC1") (pin "R31") (pinfunction "DIGPRVDD1_R31") (pintype "power_in"))
      (node (ref "R26") (pin "2") (pinfunction "2_2") (pintype "passive"))
      (node (ref "R27") (pin "2") (pinfunction "2_2") (pintype "passive"))
    )
    (net (code "3") (name "Net-(C59-Pad2)") (class "Default")
      (node (ref "C59") (pin "2") (pinfunction "2_2") (pintype "passive"))
      (node (ref "FR12") (pin "1") (pinfunction "1_1") (pintype "passive"))
      (node (ref "R28") (pin "2") (pinfunction "2_2") (pintype "passive"))
      (node (ref "R29") (pin "2") (pinfunction "2_2") (pintype "passive"))
    )
    (net (code "4") (name "Net-(C74-Pad1)") (class "Default")
      (node (ref "C74") (pin "1") (pinfunction "1_1") (pintype "passive"))
      (node (ref "C75") (pin "1") (pinfunction "1_1") (pintype "passive"))
      (node (ref "IC1") (pin "H32") (pinfunction "DIGPRVDD2_H32") (pintype "power_in"))
      (node (ref "R36") (pin "2") (pinfunction "2_2") (pintype "passive"))
    )
    (net (code "5") (name "Net-(C76-Pad1)") (class "Default")
      (node (ref "C76") (pin "1") (pinfunction "1_1") (pintype "passive"))
      (node (ref "C77") (pin "1") (pinfunction "1_1") (pintype "passive"))
      (node (ref "IC1") (pin "T32") (pinfunction "DIGPRVDD2_T32") (pintype "power_in"))
      (node (ref "R35") (pin "2") (pinfunction "2_2") (pintype "passive"))
    )
    (net (code "6") (name "Net-(C78-Pad1)") (class "Default")
      (node (ref "C78") (pin "1") (pinfunction "1_1") (pintype "passive"))
      (node (ref "C79") (pin "1") (pinfunction "1_1") (pintype "passive"))
      (node (ref "IC1") (pin "W33") (pinfunction "DIGPRVDD2_W33") (pintype "power_in"))
      (node (ref "R34") (pin "2") (pinfunction "2_2") (pintype "passive"))
    )
    (net (code "7") (name "Net-(C80-Pad1)") (class "Default")
      (node (ref "C80") (pin "1") (pinfunction "1_1") (pintype "passive"))
      (node (ref "C81") (pin "1") (pinfunction "1_1") (pintype "passive"))
      (node (ref "IC1") (pin "AH30") (pinfunction "DIGPRVDD2_AH30") (pintype "power_in"))
      (node (ref "R32") (pin "2") (pinfunction "2_2") (pintype "passive"))
    )
    (net (code "8") (name "Net-(C95-Pad1)") (class "Default")
      (node (ref "C95") (pin "1") (pinfunction "1_1") (pintype "passive"))
      (node (ref "FR34") (pin "2") (pinfunction "2_2") (pintype "passive"))
      (node (ref "R41") (pin "2") (pinfunction "2_2") (pintype "passive"))
    )
    (net (code "9") (name "Net-(C96-Pad1)") (class "Default")
      (node (ref "C96") (pin "1") (pinfunction "1_1") (pintype "passive"))
      (node (ref "FR33") (pin "1") (pinfunction "1_1") (pintype "passive"))
      (node (ref "R40") (pin "1") (pinfunction "1_1") (pintype "passive"))
    )
    (net (code "10") (name "Net-(IC1E-DIGPRPOC)") (class "Default")
      (node (ref "C72") (pin "1") (pinfunction "1_1") (pintype "passive"))
      (node (ref "C73") (pin "1") (pinfunction "1_1") (pintype "passive"))
      (node (ref "IC1") (pin "W31") (pinfunction "DIGPRPOC_W31") (pintype "power_in"))
      (node (ref "R37") (pin "2") (pinfunction "2_2") (pintype "passive"))
    )
    (net (code "11") (name "Net-(IC1E-VDD18_BIAS)") (class "Default")
      (node (ref "C88") (pin "1") (pinfunction "1_1") (pintype "passive"))
      (node (ref "FR30") (pin "1") (pinfunction "1_1") (pintype "passive"))
      (node (ref "IC1") (pin "E17") (pinfunction "VDD18_BIAS_E17") (pintype "power_in"))
    )
    (net (code "12") (name "Net-(IC1E-VDD18_DIG)") (class "Default")
      (node (ref "C67") (pin "1") (pinfunction "1_1") (pintype "passive"))
      (node (ref "IC1") (pin "D24") (pinfunction "VDD18_DIG_D24") (pintype "power_in"))
      (node (ref "R30") (pin "1") (pinfunction "1_1") (pintype "passive"))
    )
    (net (code "13") (name "Net-(IC1E-VDD18_LDO_RX)") (class "Default")
      (node (ref "C91") (pin "1") (pinfunction "1_1") (pintype "passive"))
      (node (ref "FR27") (pin "2") (pinfunction "2_2") (pintype "passive"))
      (node (ref "IC1") (pin "AE3") (pinfunction "VDD18_TIA_RFE_AE3") (pintype "power_in"))
      (node (ref "IC1") (pin "AF4") (pinfunction "VDD18_LDO_RX_AF4") (pintype "power_in"))
    )
    (net (code "14") (name "Net-(IC1E-VDD18_LDO_TX)") (class "Default")
      (node (ref "C92") (pin "1") (pinfunction "1_1") (pintype "passive"))
      (node (ref "FR26") (pin "2") (pinfunction "2_2") (pintype "passive"))
      (node (ref "IC1") (pin "N1") (pinfunction "VDD18_LDO_TX_N1") (pintype "power_in"))
    )
    (net (code "15") (name "Net-(IC1E-VDD18_RXBUF)") (class "Default")
      (node (ref "C93") (pin "1") (pinfunction "1_1") (pintype "passive"))
      (node (ref "FR34") (pin "1") (pinfunction "1_1") (pintype "passive"))
      (node (ref "IC1") (pin "AM26") (pinfunction "VDD18_RXBUF_AM26") (pintype "power_in"))
    )
    (net (code "16") (name "Net-(IC1E-VDD18_SXR)") (class "Default")
      (node (ref "C90") (pin "1") (pinfunction "1_1") (pintype "passive"))
      (node (ref "FR28") (pin "1") (pinfunction "1_1") (pintype "passive"))
      (node (ref "IC1") (pin "AM18") (pinfunction "VDD18_SXR_AM18") (pintype "power_in"))
    )
    (net (code "17") (name "Net-(IC1E-VDD18_TRF)") (class "Default")
      (node (ref "C87") (pin "1") (pinfunction "1_1") (pintype "passive"))
      (node (ref "FR31") (pin "1") (pinfunction "1_1") (pintype "passive"))
      (node (ref "IC1") (pin "D16") (pinfunction "VDD18_TRF_D16") (pintype "power_in"))
    )
    (net (code "18") (name "Net-(IC1E-VDD18_TXBUF)") (class "Default")
      (node (ref "C94") (pin "1") (pinfunction "1_1") (pintype "passive"))
      (node (ref "FR33") (pin "2") (pinfunction "2_2") (pintype "passive"))
      (node (ref "IC1") (pin "H6") (pinfunction "VDD18_TXBUF_H6") (pintype "power_in"))
    )
    (net (code "19") (name "Net-(IC1E-VDD18_VCO_CGEN)") (class "Default")
      (node (ref "C86") (pin "1") (pinfunction "1_1") (pintype "passive"))
      (node (ref "FR32") (pin "1") (pinfunction "1_1") (pintype "passive"))
      (node (ref "IC1") (pin "E21") (pinfunction "VDD18_VCO_CGEN_E21") (pintype "power_in"))
    )
    (net (code "20") (name "Net-(IC1E-VDD18_VCO_SXR)") (class "Default")
      (node (ref "C89") (pin "1") (pinfunction "1_1") (pintype "passive"))
      (node (ref "FR29") (pin "1") (pinfunction "1_1") (pintype "passive"))
      (node (ref "IC1") (pin "AK22") (pinfunction "VDD18_VCO_SXR_AK22") (pintype "power_in"))
    )
    (net (code "21") (name "Net-(IC1E-VDD18_VCO_SXT)") (class "Default")
      (node (ref "C85") (pin "1") (pinfunction "1_1") (pintype "passive"))
      (node (ref "FR24") (pin "1") (pinfunction "1_1") (pintype "passive"))
      (node (ref "IC1") (pin "G3") (pinfunction "VDD18_VCO_SXT_G3") (pintype "power_in"))
    )
    (net (code "22") (name "Net-(IC1F-DVDD_CGEN)") (class "Default")
      (node (ref "C32") (pin "1") (pinfunction "1_1") (pintype "passive"))
      (node (ref "C33") (pin "1") (pinfunction "1_1") (pintype "passive"))
      (node (ref "C34") (pin "1") (pinfunction "1_1") (pintype "passive"))
      (node (ref "FR3") (pin "1") (pinfunction "1_1") (pintype "passive"))
      (node (ref "IC1") (pin "A17") (pinfunction "DVDD_CGEN_A17") (pintype "power_in"))
      (node (ref "IC1") (pin "C25") (pinfunction "VDD12_DIG_C25") (pintype "power_in"))
      (node (ref "IC1") (pin "F24") (pinfunction "VDD_SPI_BUF_F24") (pintype "power_in"))
    )
    (net (code "23") (name "Net-(IC1F-DVDD_SXR)") (class "Default")
      (node (ref "C36") (pin "1") (pinfunction "1_1") (pintype "passive"))
      (node (ref "FR1") (pin "1") (pinfunction "1_1") (pintype "passive"))
      (node (ref "IC1") (pin "AL21") (pinfunction "DVDD_SXR_AL21") (pintype "power_in"))
    )
    (net (code "24") (name "Net-(IC1F-DVDD_SXT)") (class "Default")
      (node (ref "C35") (pin "2") (pinfunction "2_2") (pintype "passive"))
      (node (ref "FR2") (pin "1") (pinfunction "1_1") (pintype "passive"))
      (node (ref "IC1") (pin "M4") (pinfunction "DVDD_SXT_M4") (pintype "power_in"))
    )
    (net (code "25") (name "Net-(IC1F-VDD12O_VCO_SXT)") (class "Default")
      (node (ref "C58") (pin "2") (pinfunction "2_2") (pintype "passive"))
      (node (ref "FR4") (pin "1") (pinfunction "1_1") (pintype "passive"))
      (node (ref "IC1") (pin "J5") (pinfunction "VDD12O_VCO_SXT_J5") (pintype "power_in"))
      (node (ref "IC1") (pin "K6") (pinfunction "VDD12_VCO_SXT_K6") (pintype "power_in"))
    )
    (net (code "26") (name "Net-(IC1F-VDD12_LNA_RFE)") (class "Default")
      (node (ref "C55") (pin "1") (pinfunction "1_1") (pintype "passive"))
      (node (ref "FR8") (pin "1") (pinfunction "1_1") (pintype "passive"))
      (node (ref "IC1") (pin "AG5") (pinfunction "VDD12_LNA_RFE_AG5") (pintype "power_in"))
    )
    (net (code "27") (name "Net-(IC1F-VDD12_RXBUF)") (class "Default")
      (node (ref "C51") (pin "1") (pinfunction "1_1") (pintype "passive"))
      (node (ref "IC1") (pin "AP26") (pinfunction "VDD12_RXBUF_AP26") (pintype "power_in"))
      (node (ref "R29") (pin "1") (pinfunction "1_1") (pintype "passive"))
    )
    (net (code "28") (name "Net-(IC1F-VDD12_TIA_RFE)") (class "Default")
      (node (ref "C56") (pin "2") (pinfunction "2_2") (pintype "passive"))
      (node (ref "FR7") (pin "1") (pinfunction "1_1") (pintype "passive"))
      (node (ref "IC1") (pin "AD6") (pinfunction "VDD12_TIA_RFE_AD6") (pintype "power_in"))
    )
    (net (code "29") (name "Net-(IC1F-VDD12_TXBUF)") (class "Default")
      (node (ref "C43") (pin "1") (pinfunction "1_1") (pintype "passive"))
      (node (ref "IC1") (pin "G5") (pinfunction "VDD12_TXBUF_G5") (pintype "power_in"))
      (node (ref "R28") (pin "1") (pinfunction "1_1") (pintype "passive"))
    )
    (net (code "30") (name "Net-(IC1F-VDD12_VCO_SXR)") (class "Default")
      (node (ref "C52") (pin "1") (pinfunction "1_1") (pintype "passive"))
      (node (ref "FR11") (pin "1") (pinfunction "1_1") (pintype "passive"))
      (node (ref "IC1") (pin "AN23") (pinfunction "VDD12_VCO_SXR_AN23") (pintype "power_in"))
    )
    (net (code "31") (name "Net-(IC1F-VDD14_LNA_RFE)") (class "Default")
      (node (ref "C63") (pin "1") (pinfunction "1_1") (pintype "passive"))
      (node (ref "C64") (pin "1") (pinfunction "1_1") (pintype "passive"))
      (node (ref "C65") (pin "1") (pinfunction "1_1") (pintype "passive"))
      (node (ref "FR20") (pin "1") (pinfunction "1_1") (pintype "passive"))
      (node (ref "IC1") (pin "AD4") (pinfunction "VDD14_RBB_AD4") (pintype "power_in"))
      (node (ref "IC1") (pin "AF2") (pinfunction "VDD14_TIA_RFE_AF2") (pintype "power_in"))
      (node (ref "IC1") (pin "AF6") (pinfunction "VDD14_LNA_RFE_AF6") (pintype "power_in"))
    )
    (net (code "32") (name "Net-(IC1F-VDD14_VCO_CGEN)") (class "Default")
      (node (ref "C61") (pin "1") (pinfunction "1_1") (pintype "passive"))
      (node (ref "C62") (pin "1") (pinfunction "1_1") (pintype "passive"))
      (node (ref "FR21") (pin "1") (pinfunction "1_1") (pintype "passive"))
      (node (ref "IC1") (pin "C21") (pinfunction "VDD14_VCO_CGEN_C21") (pintype "power_in"))
    )
    (net (code "33") (name "Net-(IC1F-VDDO_DIV_SXT)") (class "Default")
      (node (ref "C60") (pin "1") (pinfunction "1_1") (pintype "passive"))
      (node (ref "FR18") (pin "1") (pinfunction "1_1") (pintype "passive"))
      (node (ref "IC1") (pin "K2") (pinfunction "VDDO_DIV_SXT_K2") (pintype "power_in"))
      (node (ref "IC1") (pin "L5") (pinfunction "VDD_DIV_SXT_L5") (pintype "power_in"))
    )
    (net (code "34") (name "Net-(IC1F-VDDO_TLOBUF_TRF)") (class "Default")
      (node (ref "C45") (pin "1") (pinfunction "1_1") (pintype "passive"))
      (node (ref "FR17") (pin "1") (pinfunction "1_1") (pintype "passive"))
      (node (ref "IC1") (pin "D6") (pinfunction "VDDO_TLOBUF_TRF_D6") (pintype "power_in"))
      (node (ref "IC1") (pin "F8") (pinfunction "VDD_TLOBUF_TRF_F8") (pintype "power_in"))
    )
    (net (code "35") (name "Net-(IC1F-VDD_AFE)") (class "Default")
      (node (ref "C50") (pin "1") (pinfunction "1_1") (pintype "passive"))
      (node (ref "FR13") (pin "1") (pinfunction "1_1") (pintype "passive"))
      (node (ref "IC1") (pin "AJ25") (pinfunction "VDD_AFE_AJ25") (pintype "power_in"))
    )
    (net (code "36") (name "Net-(IC1F-VDD_CP_CGEN)") (class "Default")
      (node (ref "C49") (pin "2") (pinfunction "2_2") (pintype "passive"))
      (node (ref "FR14") (pin "1") (pinfunction "1_1") (pintype "passive"))
      (node (ref "IC1") (pin "F20") (pinfunction "VDD_CP_CGEN_F20") (pintype "power_in"))
    )
    (net (code "37") (name "Net-(IC1F-VDD_CP_SXR)") (class "Default")
      (node (ref "C54") (pin "1") (pinfunction "1_1") (pintype "passive"))
      (node (ref "FR9") (pin "1") (pinfunction "1_1") (pintype "passive"))
      (node (ref "IC1") (pin "AL19") (pinfunction "VDD_CP_SXR_AL19") (pintype "power_in"))
    )
    (net (code "38") (name "Net-(IC1F-VDD_CP_SXT)") (class "Default")
      (node (ref "C57") (pin "1") (pinfunction "1_1") (pintype "passive"))
      (node (ref "FR5") (pin "1") (pinfunction "1_1") (pintype "passive"))
      (node (ref "IC1") (pin "J3") (pinfunction "VDD_CP_SXT_J3") (pintype "power_in"))
    )
    (net (code "39") (name "Net-(IC1F-VDD_DIV_CGEN)") (class "Default")
      (node (ref "C47") (pin "1") (pinfunction "1_1") (pintype "passive"))
      (node (ref "C48") (pin "1") (pinfunction "1_1") (pintype "passive"))
      (node (ref "FR15") (pin "1") (pinfunction "1_1") (pintype "passive"))
      (node (ref "IC1") (pin "E19") (pinfunction "VDD_DIV_CGEN_E19") (pintype "power_in"))
    )
    (net (code "40") (name "Net-(IC1F-VDD_DIV_SXR)") (class "Default")
      (node (ref "C53") (pin "1") (pinfunction "1_1") (pintype "passive"))
      (node (ref "FR10") (pin "1") (pinfunction "1_1") (pintype "passive"))
      (node (ref "IC1") (pin "AM20") (pinfunction "VDD_DIV_SXR_AM20") (pintype "power_in"))
    )
    (net (code "41") (name "Net-(IC1F-VDD_MXLOBUF_RFE)") (class "Default")
      (node (ref "C66") (pin "1") (pinfunction "1_1") (pintype "passive"))
      (node (ref "FR19") (pin "1") (pinfunction "1_1") (pintype "passive"))
      (node (ref "IC1") (pin "AN17") (pinfunction "VDD_MXLOBUF_RFE_AN17") (pintype "power_in"))
    )
    (net (code "42") (name "Net-(IC1F-VDD_TBB)") (class "Default")
      (node (ref "C44") (pin "1") (pinfunction "1_1") (pintype "passive"))
      (node (ref "FR6") (pin "1") (pinfunction "1_1") (pintype "passive"))
      (node (ref "IC1") (pin "P4") (pinfunction "VDD_TBB_P4") (pintype "power_in"))
    )
    (net (code "43") (name "Net-(IC1F-VDD_TPAD_TRF)") (class "Default")
      (node (ref "C46") (pin "1") (pinfunction "1_1") (pintype "passive"))
      (node (ref "FR16") (pin "1") (pinfunction "1_1") (pintype "passive"))
      (node (ref "IC1") (pin "B16") (pinfunction "VDD_TPAD_TRF_B16") (pintype "power_in"))
    )
    (net (code "44") (name "Net-(IC5-ADJ)") (class "Default")
      (node (ref "IC5") (pin "5") (pinfunction "ADJ_5") (pintype "input"))
      (node (ref "R31") (pin "1") (pinfunction "1_1") (pintype "passive"))
      (node (ref "R33") (pin "2") (pinfunction "2_2") (pintype "passive"))
    )
    (net (code "45") (name "Net-(IC5-EN)") (class "Default")
      (node (ref "C68") (pin "2") (pinfunction "2_2") (pintype "passive"))
      (node (ref "FR22") (pin "2") (pinfunction "2_2") (pintype "passive"))
      (node (ref "IC5") (pin "1") (pinfunction "EN_1") (pintype "input"))
      (node (ref "IC5") (pin "6") (pinfunction "Vin_6") (pintype "input"))
    )
    (net (code "46") (name "Net-(IC5-PG)") (class "Default")
      (node (ref "C71") (pin "2") (pinfunction "2_2") (pintype "passive"))
      (node (ref "IC5") (pin "3") (pinfunction "PG_3") (pintype "output"))
    )
    (net (code "47") (name "Net-(IC6-ADJ)") (class "Default")
      (node (ref "IC6") (pin "5") (pinfunction "ADJ_5") (pintype "input"))
      (node (ref "R38") (pin "1") (pinfunction "1_1") (pintype "passive"))
      (node (ref "R39") (pin "2") (pinfunction "2_2") (pintype "passive"))
    )
    (net (code "48") (name "Net-(IC6-EN)") (class "Default")
      (node (ref "C82") (pin "2") (pinfunction "2_2") (pintype "passive"))
      (node (ref "FR25") (pin "2") (pinfunction "2_2") (pintype "passive"))
      (node (ref "IC6") (pin "1") (pinfunction "EN_1") (pintype "input"))
      (node (ref "IC6") (pin "6") (pinfunction "Vin_6") (pintype "input"))
    )
    (net (code "49") (name "Net-(IC6-PG)") (class "Default")
      (node (ref "C84") (pin "2") (pinfunction "2_2") (pintype "passive"))
      (node (ref "IC6") (pin "3") (pinfunction "PG_3") (pintype "output"))
    )
    (net (code "50") (name "VCC1P4_LMS") (class "Default")
      (node (ref "C83") (pin "2") (pinfunction "2_2") (pintype "passive"))
      (node (ref "FR18") (pin "2") (pinfunction "2_2") (pintype "passive"))
      (node (ref "FR19") (pin "2") (pinfunction "2_2") (pintype "passive"))
      (node (ref "FR20") (pin "2") (pinfunction "2_2") (pintype "passive"))
      (node (ref "FR21") (pin "2") (pinfunction "2_2") (pintype "passive"))
      (node (ref "IC6") (pin "4") (pinfunction "Vout_4") (pintype "output"))
      (node (ref "R26") (pin "1") (pinfunction "1_1") (pintype "passive"))
      (node (ref "R38") (pin "2") (pinfunction "2_2") (pintype "passive"))
    )
    (net (code "51") (name "VCC1P8") (class "Default")
      (node (ref "FR23") (pin "1") (pinfunction "1_1") (pintype "passive"))
    )
    (net (code "52") (name "VCC1P8_LMS") (class "Default")
      (node (ref "C70") (pin "2") (pinfunction "2_2") (pintype "passive"))
      (node (ref "FR22") (pin "1") (pinfunction "1_1") (pintype "passive"))
      (node (ref "FR23") (pin "2") (pinfunction "2_2") (pintype "passive"))
      (node (ref "FR24") (pin "2") (pinfunction "2_2") (pintype "passive"))
      (node (ref "FR25") (pin "1") (pinfunction "1_1") (pintype "passive"))
      (node (ref "FR26") (pin "1") (pinfunction "1_1") (pintype "passive"))
      (node (ref "FR27") (pin "1") (pinfunction "1_1") (pintype "passive"))
      (node (ref "FR28") (pin "2") (pinfunction "2_2") (pintype "passive"))
      (node (ref "FR29") (pin "2") (pinfunction "2_2") (pintype "passive"))
      (node (ref "FR30") (pin "2") (pinfunction "2_2") (pintype "passive"))
      (node (ref "FR31") (pin "2") (pinfunction "2_2") (pintype "passive"))
      (node (ref "FR32") (pin "2") (pinfunction "2_2") (pintype "passive"))
      (node (ref "R30") (pin "2") (pinfunction "2_2") (pintype "passive"))
      (node (ref "R40") (pin "2") (pinfunction "2_2") (pintype "passive"))
      (node (ref "R41") (pin "1") (pinfunction "1_1") (pintype "passive"))
    )
    (net (code "53") (name "VCC1P25_LMS") (class "Default")
      (node (ref "C69") (pin "2") (pinfunction "2_2") (pintype "passive"))
      (node (ref "FR1") (pin "2") (pinfunction "2_2") (pintype "passive"))
      (node (ref "FR10") (pin "2") (pinfunction "2_2") (pintype "passive"))
      (node (ref "FR11") (pin "2") (pinfunction "2_2") (pintype "passive"))
      (node (ref "FR12") (pin "2") (pinfunction "2_2") (pintype "passive"))
      (node (ref "FR13") (pin "2") (pinfunction "2_2") (pintype "passive"))
      (node (ref "FR14") (pin "2") (pinfunction "2_2") (pintype "passive"))
      (node (ref "FR15") (pin "2") (pinfunction "2_2") (pintype "passive"))
      (node (ref "FR16") (pin "2") (pinfunction "2_2") (pintype "passive"))
      (node (ref "FR17") (pin "2") (pinfunction "2_2") (pintype "passive"))
      (node (ref "FR2") (pin "2") (pinfunction "2_2") (pintype "passive"))
      (node (ref "FR3") (pin "2") (pinfunction "2_2") (pintype "passive"))
      (node (ref "FR4") (pin "2") (pinfunction "2_2") (pintype "passive"))
      (node (ref "FR5") (pin "2") (pinfunction "2_2") (pintype "passive"))
      (node (ref "FR6") (pin "2") (pinfunction "2_2") (pintype "passive"))
      (node (ref "FR7") (pin "2") (pinfunction "2_2") (pintype "passive"))
      (node (ref "FR8") (pin "2") (pinfunction "2_2") (pintype "passive"))
      (node (ref "FR9") (pin "2") (pinfunction "2_2") (pintype "passive"))
      (node (ref "IC5") (pin "4") (pinfunction "Vout_4") (pintype "output"))
      (node (ref "R27") (pin "1") (pinfunction "1_1") (pintype "passive"))
      (node (ref "R31") (pin "2") (pinfunction "2_2") (pintype "passive"))
    )
    (net (code "54") (name "VDIO_LMS") (class "Default")
      (node (ref "R32") (pin "1") (pinfunction "1_1") (pintype "passive"))
      (node (ref "R34") (pin "1") (pinfunction "1_1") (pintype "passive"))
      (node (ref "R35") (pin "1") (pinfunction "1_1") (pintype "passive"))
      (node (ref "R36") (pin "1") (pinfunction "1_1") (pintype "passive"))
      (node (ref "R37") (pin "1") (pinfunction "1_1") (pintype "passive"))
    )
  )
)
